# AnalogTransform.net
KiCad netlist of a schematic drawn in Altium Designer
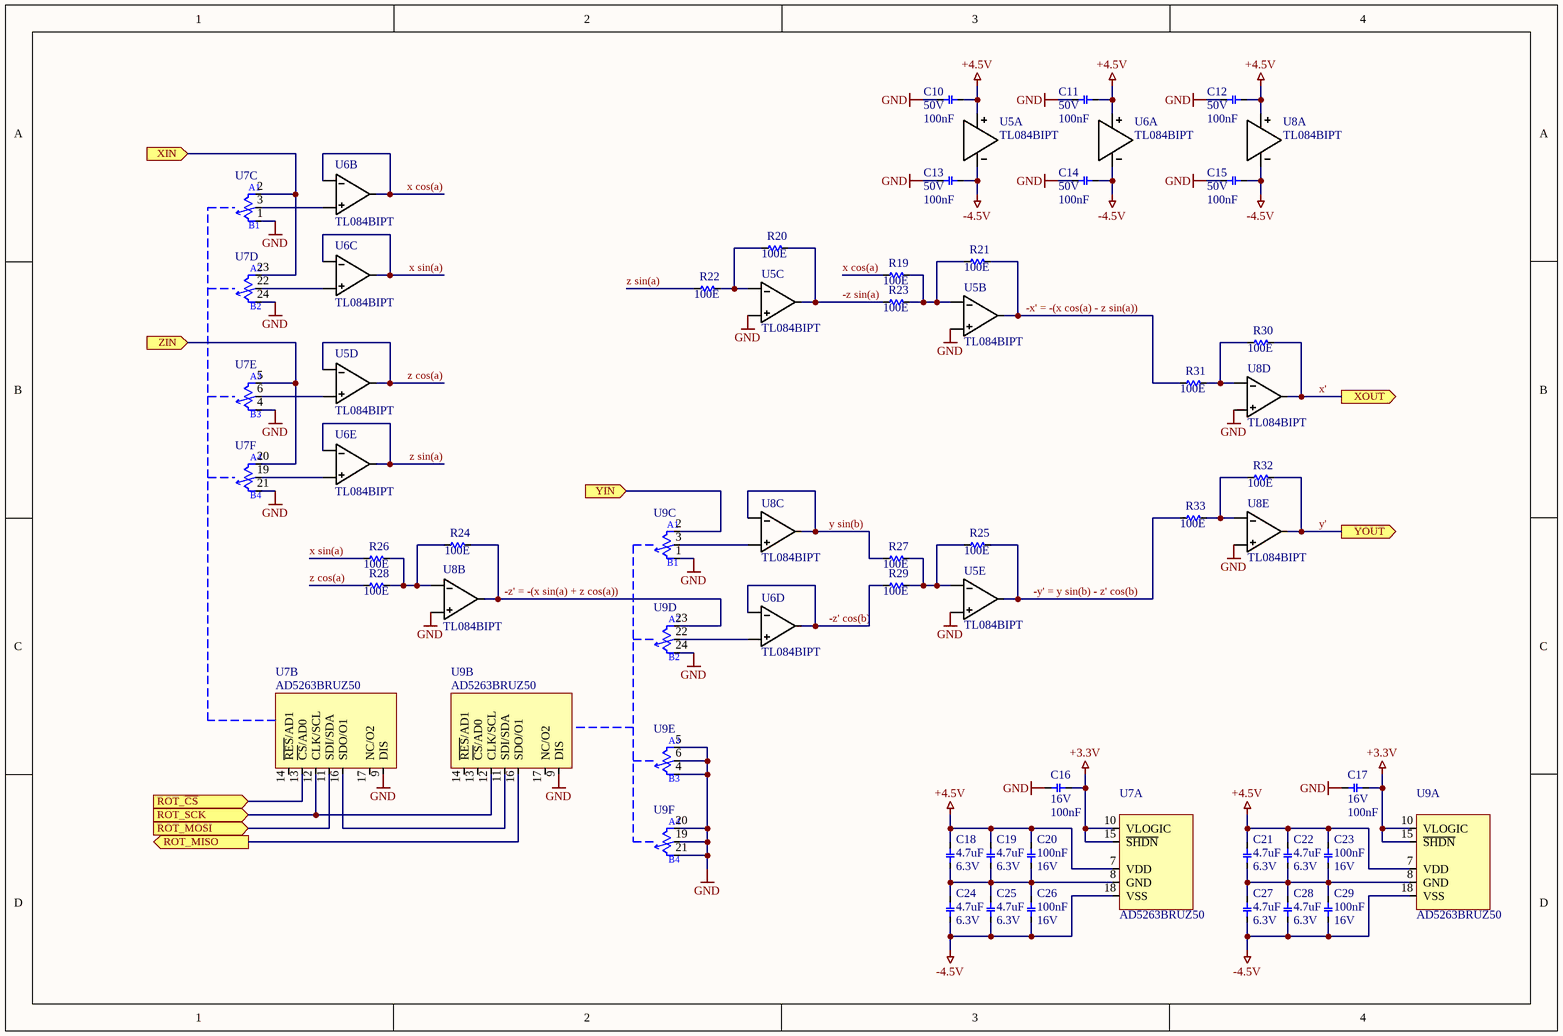
[diagram p0: AnalogTransform.SchDoc]

(export (version "E")
  (design (tool "Eeschema 10.0.6"))
  (components
    (comp (ref "C10")
      (value "100nF")
      (footprint "CX7R0402C")
      (description "SMD Capacitor")
      (fields (field (name "VALUE2") "50V") (field (name "Comment") "04025C104JAT2A"))
      (libsource (lib "ChaoticCircuits") (part "kyocera-C-X7R-0402"))
    )
    (comp (ref "C11")
      (value "100nF")
      (footprint "CX7R0402C")
      (description "SMD Capacitor")
      (fields (field (name "VALUE2") "50V") (field (name "Comment") "04025C104JAT2A"))
      (libsource (lib "ChaoticCircuits") (part "kyocera-C-X7R-0402"))
    )
    (comp (ref "C12")
      (value "100nF")
      (footprint "CX7R0402C")
      (description "SMD Capacitor")
      (fields (field (name "VALUE2") "50V") (field (name "Comment") "04025C104JAT2A"))
      (libsource (lib "ChaoticCircuits") (part "kyocera-C-X7R-0402"))
    )
    (comp (ref "C13")
      (value "100nF")
      (footprint "CX7R0402C")
      (description "SMD Capacitor")
      (fields (field (name "VALUE2") "50V") (field (name "Comment") "04025C104JAT2A"))
      (libsource (lib "ChaoticCircuits") (part "kyocera-C-X7R-0402"))
    )
    (comp (ref "C14")
      (value "100nF")
      (footprint "CX7R0402C")
      (description "SMD Capacitor")
      (fields (field (name "VALUE2") "50V") (field (name "Comment") "04025C104JAT2A"))
      (libsource (lib "ChaoticCircuits") (part "kyocera-C-X7R-0402"))
    )
    (comp (ref "C15")
      (value "100nF")
      (footprint "CX7R0402C")
      (description "SMD Capacitor")
      (fields (field (name "VALUE2") "50V") (field (name "Comment") "04025C104JAT2A"))
      (libsource (lib "ChaoticCircuits") (part "kyocera-C-X7R-0402"))
    )
    (comp (ref "C16")
      (value "100nF")
      (footprint "CX7R0402C")
      (description "SMD Capacitor")
      (fields (field (name "VALUE2") "16V") (field (name "Comment") "0402YC104JAT2A"))
      (libsource (lib "ChaoticCircuits") (part "kyocera-C-X7R-0402"))
    )
    (comp (ref "C17")
      (value "100nF")
      (footprint "CX7R0402C")
      (description "SMD Capacitor")
      (fields (field (name "VALUE2") "16V") (field (name "Comment") "0402YC104JAT2A"))
      (libsource (lib "ChaoticCircuits") (part "kyocera-C-X7R-0402"))
    )
    (comp (ref "C18")
      (value "4.7uF")
      (footprint "CX7R0603K")
      (description "SMD Capacitor")
      (fields (field (name "VALUE2") "6.3V") (field (name "Comment") "06036C475JAT2A"))
      (libsource (lib "ChaoticCircuits") (part "kyocera-C-X7R-0603"))
    )
    (comp (ref "C19")
      (value "4.7uF")
      (footprint "CX7R0603K")
      (description "SMD Capacitor")
      (fields (field (name "VALUE2") "6.3V") (field (name "Comment") "06036C475JAT2A"))
      (libsource (lib "ChaoticCircuits") (part "kyocera-C-X7R-0603"))
    )
    (comp (ref "C20")
      (value "100nF")
      (footprint "CX7R0402C")
      (description "SMD Capacitor")
      (fields (field (name "VALUE2") "16V") (field (name "Comment") "0402YC104JAT2A"))
      (libsource (lib "ChaoticCircuits") (part "kyocera-C-X7R-0402"))
    )
    (comp (ref "C21")
      (value "4.7uF")
      (footprint "CX7R0603K")
      (description "SMD Capacitor")
      (fields (field (name "VALUE2") "6.3V") (field (name "Comment") "06036C475JAT2A"))
      (libsource (lib "ChaoticCircuits") (part "kyocera-C-X7R-0603"))
    )
    (comp (ref "C22")
      (value "4.7uF")
      (footprint "CX7R0603K")
      (description "SMD Capacitor")
      (fields (field (name "VALUE2") "6.3V") (field (name "Comment") "06036C475JAT2A"))
      (libsource (lib "ChaoticCircuits") (part "kyocera-C-X7R-0603"))
    )
    (comp (ref "C23")
      (value "100nF")
      (footprint "CX7R0402C")
      (description "SMD Capacitor")
      (fields (field (name "VALUE2") "16V") (field (name "Comment") "0402YC104JAT2A"))
      (libsource (lib "ChaoticCircuits") (part "kyocera-C-X7R-0402"))
    )
    (comp (ref "C24")
      (value "4.7uF")
      (footprint "CX7R0603K")
      (description "SMD Capacitor")
      (fields (field (name "VALUE2") "6.3V") (field (name "Comment") "06036C475JAT2A"))
      (libsource (lib "ChaoticCircuits") (part "kyocera-C-X7R-0603"))
    )
    (comp (ref "C25")
      (value "4.7uF")
      (footprint "CX7R0603K")
      (description "SMD Capacitor")
      (fields (field (name "VALUE2") "6.3V") (field (name "Comment") "06036C475JAT2A"))
      (libsource (lib "ChaoticCircuits") (part "kyocera-C-X7R-0603"))
    )
    (comp (ref "C26")
      (value "100nF")
      (footprint "CX7R0402C")
      (description "SMD Capacitor")
      (fields (field (name "VALUE2") "16V") (field (name "Comment") "0402YC104JAT2A"))
      (libsource (lib "ChaoticCircuits") (part "kyocera-C-X7R-0402"))
    )
    (comp (ref "C27")
      (value "4.7uF")
      (footprint "CX7R0603K")
      (description "SMD Capacitor")
      (fields (field (name "VALUE2") "6.3V") (field (name "Comment") "06036C475JAT2A"))
      (libsource (lib "ChaoticCircuits") (part "kyocera-C-X7R-0603"))
    )
    (comp (ref "C28")
      (value "4.7uF")
      (footprint "CX7R0603K")
      (description "SMD Capacitor")
      (fields (field (name "VALUE2") "6.3V") (field (name "Comment") "06036C475JAT2A"))
      (libsource (lib "ChaoticCircuits") (part "kyocera-C-X7R-0603"))
    )
    (comp (ref "C29")
      (value "100nF")
      (footprint "CX7R0402C")
      (description "SMD Capacitor")
      (fields (field (name "VALUE2") "16V") (field (name "Comment") "0402YC104JAT2A"))
      (libsource (lib "ChaoticCircuits") (part "kyocera-C-X7R-0402"))
    )
    (comp (ref "R19")
      (value "100E")
      (footprint "RC0402")
      (description "SMD Resistor")
      (fields (field (name "Comment") "0402FR-07100RL"))
      (libsource (lib "ChaoticCircuits") (part "YAGEO-RC-0402"))
    )
    (comp (ref "R20")
      (value "100E")
      (footprint "RC0402")
      (description "SMD Resistor")
      (fields (field (name "Comment") "0402FR-07100RL"))
      (libsource (lib "ChaoticCircuits") (part "YAGEO-RC-0402"))
    )
    (comp (ref "R21")
      (value "100E")
      (footprint "RC0402")
      (description "SMD Resistor")
      (fields (field (name "Comment") "0402FR-07100RL"))
      (libsource (lib "ChaoticCircuits") (part "YAGEO-RC-0402"))
    )
    (comp (ref "R22")
      (value "100E")
      (footprint "RC0402")
      (description "SMD Resistor")
      (fields (field (name "Comment") "0402FR-07100RL"))
      (libsource (lib "ChaoticCircuits") (part "YAGEO-RC-0402"))
    )
    (comp (ref "R23")
      (value "100E")
      (footprint "RC0402")
      (description "SMD Resistor")
      (fields (field (name "Comment") "0402FR-07100RL"))
      (libsource (lib "ChaoticCircuits") (part "YAGEO-RC-0402"))
    )
    (comp (ref "R24")
      (value "100E")
      (footprint "RC0402")
      (description "SMD Resistor")
      (fields (field (name "Comment") "0402FR-07100RL"))
      (libsource (lib "ChaoticCircuits") (part "YAGEO-RC-0402"))
    )
    (comp (ref "R25")
      (value "100E")
      (footprint "RC0402")
      (description "SMD Resistor")
      (fields (field (name "Comment") "0402FR-07100RL"))
      (libsource (lib "ChaoticCircuits") (part "YAGEO-RC-0402"))
    )
    (comp (ref "R26")
      (value "100E")
      (footprint "RC0402")
      (description "SMD Resistor")
      (fields (field (name "Comment") "0402FR-07100RL"))
      (libsource (lib "ChaoticCircuits") (part "YAGEO-RC-0402"))
    )
    (comp (ref "R27")
      (value "100E")
      (footprint "RC0402")
      (description "SMD Resistor")
      (fields (field (name "Comment") "0402FR-07100RL"))
      (libsource (lib "ChaoticCircuits") (part "YAGEO-RC-0402"))
    )
    (comp (ref "R28")
      (value "100E")
      (footprint "RC0402")
      (description "SMD Resistor")
      (fields (field (name "Comment") "0402FR-07100RL"))
      (libsource (lib "ChaoticCircuits") (part "YAGEO-RC-0402"))
    )
    (comp (ref "R29")
      (value "100E")
      (footprint "RC0402")
      (description "SMD Resistor")
      (fields (field (name "Comment") "0402FR-07100RL"))
      (libsource (lib "ChaoticCircuits") (part "YAGEO-RC-0402"))
    )
    (comp (ref "R30")
      (value "100E")
      (footprint "RC0402")
      (description "SMD Resistor")
      (fields (field (name "Comment") "0402FR-07100RL"))
      (libsource (lib "ChaoticCircuits") (part "YAGEO-RC-0402"))
    )
    (comp (ref "R31")
      (value "100E")
      (footprint "RC0402")
      (description "SMD Resistor")
      (fields (field (name "Comment") "0402FR-07100RL"))
      (libsource (lib "ChaoticCircuits") (part "YAGEO-RC-0402"))
    )
    (comp (ref "R32")
      (value "100E")
      (footprint "RC0402")
      (description "SMD Resistor")
      (fields (field (name "Comment") "0402FR-07100RL"))
      (libsource (lib "ChaoticCircuits") (part "YAGEO-RC-0402"))
    )
    (comp (ref "R33")
      (value "100E")
      (footprint "RC0402")
      (description "SMD Resistor")
      (fields (field (name "Comment") "0402FR-07100RL"))
      (libsource (lib "ChaoticCircuits") (part "YAGEO-RC-0402"))
    )
    (comp (ref "U5")
      (value "TL084BIPT")
      (footprint "TSSOP14_0.65_C")
      (description "J-FET Amplifier 4 Circuit - 14-TSSOP")
      (libsource (lib "ChaoticCircuits") (part "TL084"))
    )
    (comp (ref "U6")
      (value "TL084BIPT")
      (footprint "TSSOP14_0.65_C")
      (description "J-FET Amplifier 4 Circuit - 14-TSSOP")
      (libsource (lib "ChaoticCircuits") (part "TL084"))
    )
    (comp (ref "U7")
      (value "AD5263BRUZ50")
      (footprint "TSSOP24_0.65_C")
      (description "Digital Potentiometer 50k Ohm 4 Circuit 256 Taps I²C, SPI Interface 24-TSSOP")
      (libsource (lib "") (part "AD5263BRUZ50_1"))
    )
    (comp (ref "U8")
      (value "TL084BIPT")
      (footprint "TSSOP14_0.65_C")
      (description "J-FET Amplifier 4 Circuit - 14-TSSOP")
      (libsource (lib "ChaoticCircuits") (part "TL084"))
    )
    (comp (ref "U9")
      (value "AD5263BRUZ50")
      (footprint "TSSOP24_0.65_C")
      (description "Digital Potentiometer 50k Ohm 4 Circuit 256 Taps I²C, SPI Interface 24-TSSOP")
      (libsource (lib "ChaoticCircuits") (part "AD5263BRUZ50"))
    )
  )
  (nets
    (net (code "1") (name "+3.3V") (class "Default")
      (node (ref "C16") (pin "2") (pinfunction "2_2") (pintype "passive"))
      (node (ref "C17") (pin "2") (pinfunction "2_2") (pintype "passive"))
      (node (ref "U7") (pin "10") (pinfunction "VLOGIC_10") (pintype "passive"))
      (node (ref "U7") (pin "15") (pinfunction "~{SHDN}_15") (pintype "passive"))
      (node (ref "U9") (pin "10") (pinfunction "VLOGIC_10") (pintype "passive"))
      (node (ref "U9") (pin "15") (pinfunction "~{SHDN}_15") (pintype "passive"))
    )
    (net (code "2") (name "+4.5V") (class "Default")
      (node (ref "C10") (pin "2") (pinfunction "2_2") (pintype "passive"))
      (node (ref "C11") (pin "2") (pinfunction "2_2") (pintype "passive"))
      (node (ref "C12") (pin "2") (pinfunction "2_2") (pintype "passive"))
      (node (ref "C18") (pin "2") (pinfunction "2_2") (pintype "passive"))
      (node (ref "C19") (pin "2") (pinfunction "2_2") (pintype "passive"))
      (node (ref "C20") (pin "2") (pinfunction "2_2") (pintype "passive"))
      (node (ref "C21") (pin "2") (pinfunction "2_2") (pintype "passive"))
      (node (ref "C22") (pin "2") (pinfunction "2_2") (pintype "passive"))
      (node (ref "C23") (pin "2") (pinfunction "2_2") (pintype "passive"))
      (node (ref "U5") (pin "4") (pinfunction "VCC+_4") (pintype "passive"))
      (node (ref "U6") (pin "4") (pinfunction "VCC+_4") (pintype "passive"))
      (node (ref "U7") (pin "7") (pinfunction "VDD_7") (pintype "passive"))
      (node (ref "U8") (pin "4") (pinfunction "VCC+_4") (pintype "passive"))
      (node (ref "U9") (pin "7") (pinfunction "VDD_7") (pintype "passive"))
    )
    (net (code "3") (name "-4.5V") (class "Default")
      (node (ref "C13") (pin "2") (pinfunction "2_2") (pintype "passive"))
      (node (ref "C14") (pin "2") (pinfunction "2_2") (pintype "passive"))
      (node (ref "C15") (pin "2") (pinfunction "2_2") (pintype "passive"))
      (node (ref "C24") (pin "1") (pinfunction "1_1") (pintype "passive"))
      (node (ref "C25") (pin "1") (pinfunction "1_1") (pintype "passive"))
      (node (ref "C26") (pin "1") (pinfunction "1_1") (pintype "passive"))
      (node (ref "C27") (pin "1") (pinfunction "1_1") (pintype "passive"))
      (node (ref "C28") (pin "1") (pinfunction "1_1") (pintype "passive"))
      (node (ref "C29") (pin "1") (pinfunction "1_1") (pintype "passive"))
      (node (ref "U5") (pin "11") (pinfunction "VCC-_11") (pintype "passive"))
      (node (ref "U6") (pin "11") (pinfunction "VCC-_11") (pintype "passive"))
      (node (ref "U7") (pin "18") (pinfunction "VSS_18") (pintype "passive"))
      (node (ref "U8") (pin "11") (pinfunction "VCC-_11") (pintype "passive"))
      (node (ref "U9") (pin "18") (pinfunction "VSS_18") (pintype "passive"))
    )
    (net (code "4") (name "/-x' = -(x cos(a) - z sin(a))") (class "Default")
      (node (ref "R21") (pin "2") (pinfunction "2_2") (pintype "passive"))
      (node (ref "R31") (pin "1") (pinfunction "1_1") (pintype "passive"))
      (node (ref "U5") (pin "1") (pinfunction "OUT1_1") (pintype "passive"))
    )
    (net (code "5") (name "/-y' = y sin(b) - z' cos(b)") (class "Default")
      (node (ref "R25") (pin "2") (pinfunction "2_2") (pintype "passive"))
      (node (ref "R33") (pin "1") (pinfunction "1_1") (pintype "passive"))
      (node (ref "U5") (pin "14") (pinfunction "OUT4_14") (pintype "passive"))
    )
    (net (code "6") (name "/-z sin(a)") (class "Default")
      (node (ref "R20") (pin "2") (pinfunction "2_2") (pintype "passive"))
      (node (ref "R23") (pin "1") (pinfunction "1_1") (pintype "passive"))
      (node (ref "U5") (pin "7") (pinfunction "OUT2_7") (pintype "passive"))
    )
    (net (code "7") (name "/-z' = -(x sin(a) + z cos(a))") (class "Default")
      (node (ref "R24") (pin "2") (pinfunction "2_2") (pintype "passive"))
      (node (ref "U8") (pin "1") (pinfunction "OUT1_1") (pintype "passive"))
      (node (ref "U9") (pin "23") (pinfunction "A2_23") (pintype "passive"))
    )
    (net (code "8") (name "/-z' cos(b)") (class "Default")
      (node (ref "R29") (pin "1") (pinfunction "1_1") (pintype "passive"))
      (node (ref "U6") (pin "8") (pinfunction "OUT3_8") (pintype "passive"))
      (node (ref "U6") (pin "9") (pinfunction "IN3-_9") (pintype "passive"))
    )
    (net (code "9") (name "/ROT_MISO") (class "Default")
      (node (ref "U9") (pin "16") (pinfunction "SDO/O1_16") (pintype "passive"))
    )
    (net (code "10") (name "/ROT_MOSI") (class "Default")
      (node (ref "U7") (pin "11") (pinfunction "SDI/SDA_11") (pintype "passive"))
    )
    (net (code "11") (name "/ROT_SCK") (class "Default")
      (node (ref "U7") (pin "12") (pinfunction "CLK/SCL_12") (pintype "passive"))
      (node (ref "U9") (pin "12") (pinfunction "CLK/SCL_12") (pintype "passive"))
    )
    (net (code "12") (name "/ROT_~{CS}") (class "Default")
      (node (ref "U7") (pin "13") (pinfunction "~{CS}/AD0_13") (pintype "passive"))
    )
    (net (code "13") (name "/XIN") (class "Default")
      (node (ref "U7") (pin "2") (pinfunction "A1_2") (pintype "passive"))
      (node (ref "U7") (pin "23") (pinfunction "A2_23") (pintype "passive"))
    )
    (net (code "14") (name "/YIN") (class "Default")
      (node (ref "U9") (pin "2") (pinfunction "A1_2") (pintype "passive"))
    )
    (net (code "15") (name "/ZIN") (class "Default")
      (node (ref "U7") (pin "20") (pinfunction "A4_20") (pintype "passive"))
      (node (ref "U7") (pin "5") (pinfunction "A3_5") (pintype "passive"))
    )
    (net (code "16") (name "/x cos(a)") (class "Default")
      (node (ref "R19") (pin "1") (pinfunction "1_1") (pintype "passive"))
      (node (ref "U6") (pin "1") (pinfunction "OUT1_1") (pintype "passive"))
      (node (ref "U6") (pin "2") (pinfunction "IN1-_2") (pintype "passive"))
    )
    (net (code "17") (name "/x sin(a)") (class "Default")
      (node (ref "R26") (pin "1") (pinfunction "1_1") (pintype "passive"))
      (node (ref "U6") (pin "6") (pinfunction "IN2-_6") (pintype "passive"))
      (node (ref "U6") (pin "7") (pinfunction "OUT2_7") (pintype "passive"))
    )
    (net (code "18") (name "/x'") (class "Default")
      (node (ref "R30") (pin "2") (pinfunction "2_2") (pintype "passive"))
      (node (ref "U8") (pin "8") (pinfunction "OUT3_8") (pintype "passive"))
    )
    (net (code "19") (name "/y sin(b)") (class "Default")
      (node (ref "R27") (pin "1") (pinfunction "1_1") (pintype "passive"))
      (node (ref "U8") (pin "6") (pinfunction "IN2-_6") (pintype "passive"))
      (node (ref "U8") (pin "7") (pinfunction "OUT2_7") (pintype "passive"))
    )
    (net (code "20") (name "/y'") (class "Default")
      (node (ref "R32") (pin "2") (pinfunction "2_2") (pintype "passive"))
      (node (ref "U8") (pin "14") (pinfunction "OUT4_14") (pintype "passive"))
    )
    (net (code "21") (name "/z cos(a)") (class "Default")
      (node (ref "R28") (pin "1") (pinfunction "1_1") (pintype "passive"))
      (node (ref "U5") (pin "8") (pinfunction "OUT3_8") (pintype "passive"))
      (node (ref "U5") (pin "9") (pinfunction "IN3-_9") (pintype "passive"))
    )
    (net (code "22") (name "/z sin(a)") (class "Default")
      (node (ref "R22") (pin "1") (pinfunction "1_1") (pintype "passive"))
      (node (ref "U6") (pin "13") (pinfunction "IN4-_13") (pintype "passive"))
      (node (ref "U6") (pin "14") (pinfunction "OUT4_14") (pintype "passive"))
    )
    (net (code "23") (name "GND") (class "Default")
      (node (ref "C10") (pin "1") (pinfunction "1_1") (pintype "passive"))
      (node (ref "C11") (pin "1") (pinfunction "1_1") (pintype "passive"))
      (node (ref "C12") (pin "1") (pinfunction "1_1") (pintype "passive"))
      (node (ref "C13") (pin "1") (pinfunction "1_1") (pintype "passive"))
      (node (ref "C14") (pin "1") (pinfunction "1_1") (pintype "passive"))
      (node (ref "C15") (pin "1") (pinfunction "1_1") (pintype "passive"))
      (node (ref "C16") (pin "1") (pinfunction "1_1") (pintype "passive"))
      (node (ref "C17") (pin "1") (pinfunction "1_1") (pintype "passive"))
      (node (ref "U5") (pin "12") (pinfunction "IN4+_12") (pintype "passive"))
      (node (ref "U5") (pin "3") (pinfunction "IN1+_3") (pintype "passive"))
      (node (ref "U5") (pin "5") (pinfunction "IN2+_5") (pintype "passive"))
      (node (ref "U7") (pin "1") (pinfunction "B1_1") (pintype "passive"))
      (node (ref "U7") (pin "21") (pinfunction "B4_21") (pintype "passive"))
      (node (ref "U7") (pin "24") (pinfunction "B2_24") (pintype "passive"))
      (node (ref "U7") (pin "4") (pinfunction "B3_4") (pintype "passive"))
      (node (ref "U7") (pin "9") (pinfunction "DIS_9") (pintype "passive"))
      (node (ref "U8") (pin "10") (pinfunction "IN3+_10") (pintype "passive"))
      (node (ref "U8") (pin "12") (pinfunction "IN4+_12") (pintype "passive"))
      (node (ref "U8") (pin "3") (pinfunction "IN1+_3") (pintype "passive"))
      (node (ref "U9") (pin "1") (pinfunction "B1_1") (pintype "passive"))
      (node (ref "U9") (pin "19") (pinfunction "W4_19") (pintype "passive"))
      (node (ref "U9") (pin "20") (pinfunction "A4_20") (pintype "passive"))
      (node (ref "U9") (pin "21") (pinfunction "B4_21") (pintype "passive"))
      (node (ref "U9") (pin "24") (pinfunction "B2_24") (pintype "passive"))
      (node (ref "U9") (pin "4") (pinfunction "B3_4") (pintype "passive"))
      (node (ref "U9") (pin "5") (pinfunction "A3_5") (pintype "passive"))
      (node (ref "U9") (pin "6") (pinfunction "W3_6") (pintype "passive"))
      (node (ref "U9") (pin "9") (pinfunction "DIS_9") (pintype "passive"))
    )
    (net (code "24") (name "Net-(U5B-IN1-)") (class "Default")
      (node (ref "R19") (pin "2") (pinfunction "2_2") (pintype "passive"))
      (node (ref "R21") (pin "1") (pinfunction "1_1") (pintype "passive"))
      (node (ref "R23") (pin "2") (pinfunction "2_2") (pintype "passive"))
      (node (ref "U5") (pin "2") (pinfunction "IN1-_2") (pintype "passive"))
    )
    (net (code "25") (name "Net-(U5C-IN2-)") (class "Default")
      (node (ref "R20") (pin "1") (pinfunction "1_1") (pintype "passive"))
      (node (ref "R22") (pin "2") (pinfunction "2_2") (pintype "passive"))
      (node (ref "U5") (pin "6") (pinfunction "IN2-_6") (pintype "passive"))
    )
    (net (code "26") (name "Net-(U5D-IN3+)") (class "Default")
      (node (ref "U5") (pin "10") (pinfunction "IN3+_10") (pintype "passive"))
      (node (ref "U7") (pin "6") (pinfunction "W3_6") (pintype "passive"))
    )
    (net (code "27") (name "Net-(U5E-IN4-)") (class "Default")
      (node (ref "R25") (pin "1") (pinfunction "1_1") (pintype "passive"))
      (node (ref "R27") (pin "2") (pinfunction "2_2") (pintype "passive"))
      (node (ref "R29") (pin "2") (pinfunction "2_2") (pintype "passive"))
      (node (ref "U5") (pin "13") (pinfunction "IN4-_13") (pintype "passive"))
    )
    (net (code "28") (name "Net-(U6B-IN1+)") (class "Default")
      (node (ref "U6") (pin "3") (pinfunction "IN1+_3") (pintype "passive"))
      (node (ref "U7") (pin "3") (pinfunction "W1_3") (pintype "passive"))
    )
    (net (code "29") (name "Net-(U6C-IN2+)") (class "Default")
      (node (ref "U6") (pin "5") (pinfunction "IN2+_5") (pintype "passive"))
      (node (ref "U7") (pin "22") (pinfunction "W2_22") (pintype "passive"))
    )
    (net (code "30") (name "Net-(U6D-IN3+)") (class "Default")
      (node (ref "U6") (pin "10") (pinfunction "IN3+_10") (pintype "passive"))
      (node (ref "U9") (pin "22") (pinfunction "W2_22") (pintype "passive"))
    )
    (net (code "31") (name "Net-(U6E-IN4+)") (class "Default")
      (node (ref "U6") (pin "12") (pinfunction "IN4+_12") (pintype "passive"))
      (node (ref "U7") (pin "19") (pinfunction "W4_19") (pintype "passive"))
    )
    (net (code "32") (name "Net-(U7A-GND)") (class "Default")
      (node (ref "C18") (pin "1") (pinfunction "1_1") (pintype "passive"))
      (node (ref "C19") (pin "1") (pinfunction "1_1") (pintype "passive"))
      (node (ref "C20") (pin "1") (pinfunction "1_1") (pintype "passive"))
      (node (ref "C24") (pin "2") (pinfunction "2_2") (pintype "passive"))
      (node (ref "C25") (pin "2") (pinfunction "2_2") (pintype "passive"))
      (node (ref "C26") (pin "2") (pinfunction "2_2") (pintype "passive"))
      (node (ref "U7") (pin "8") (pinfunction "GND_8") (pintype "passive"))
    )
    (net (code "33") (name "Net-(U7B-SDO{slash}O1)") (class "Default")
      (node (ref "U7") (pin "16") (pinfunction "SDO/O1_16") (pintype "passive"))
      (node (ref "U9") (pin "11") (pinfunction "SDI/SDA_11") (pintype "passive"))
    )
    (net (code "34") (name "Net-(U8B-IN1-)") (class "Default")
      (node (ref "R24") (pin "1") (pinfunction "1_1") (pintype "passive"))
      (node (ref "R26") (pin "2") (pinfunction "2_2") (pintype "passive"))
      (node (ref "R28") (pin "2") (pinfunction "2_2") (pintype "passive"))
      (node (ref "U8") (pin "2") (pinfunction "IN1-_2") (pintype "passive"))
    )
    (net (code "35") (name "Net-(U8C-IN2+)") (class "Default")
      (node (ref "U8") (pin "5") (pinfunction "IN2+_5") (pintype "passive"))
      (node (ref "U9") (pin "3") (pinfunction "W1_3") (pintype "passive"))
    )
    (net (code "36") (name "Net-(U8D-IN3-)") (class "Default")
      (node (ref "R30") (pin "1") (pinfunction "1_1") (pintype "passive"))
      (node (ref "R31") (pin "2") (pinfunction "2_2") (pintype "passive"))
      (node (ref "U8") (pin "9") (pinfunction "IN3-_9") (pintype "passive"))
    )
    (net (code "37") (name "Net-(U8E-IN4-)") (class "Default")
      (node (ref "R32") (pin "1") (pinfunction "1_1") (pintype "passive"))
      (node (ref "R33") (pin "2") (pinfunction "2_2") (pintype "passive"))
      (node (ref "U8") (pin "13") (pinfunction "IN4-_13") (pintype "passive"))
    )
    (net (code "38") (name "Net-(U9A-GND)") (class "Default")
      (node (ref "C21") (pin "1") (pinfunction "1_1") (pintype "passive"))
      (node (ref "C22") (pin "1") (pinfunction "1_1") (pintype "passive"))
      (node (ref "C23") (pin "1") (pinfunction "1_1") (pintype "passive"))
      (node (ref "C27") (pin "2") (pinfunction "2_2") (pintype "passive"))
      (node (ref "C28") (pin "2") (pinfunction "2_2") (pintype "passive"))
      (node (ref "C29") (pin "2") (pinfunction "2_2") (pintype "passive"))
      (node (ref "U9") (pin "8") (pinfunction "GND_8") (pintype "passive"))
    )
    (net (code "39") (name "unconnected-(U7B-NC{slash}O2-Pad17)") (class "Default")
      (node (ref "U7") (pin "17") (pinfunction "NC/O2_17") (pintype "passive"))
    )
    (net (code "40") (name "unconnected-(U7B-~{RES}{slash}AD1-Pad14)") (class "Default")
      (node (ref "U7") (pin "14") (pinfunction "~{RES}/AD1_14") (pintype "passive"))
    )
    (net (code "41") (name "unconnected-(U9B-NC{slash}O2-Pad17)") (class "Default")
      (node (ref "U9") (pin "17") (pinfunction "NC/O2_17") (pintype "passive"))
    )
    (net (code "42") (name "unconnected-(U9B-~{CS}{slash}AD0-Pad13)") (class "Default")
      (node (ref "U9") (pin "13") (pinfunction "~{CS}/AD0_13") (pintype "passive"))
    )
    (net (code "43") (name "unconnected-(U9B-~{RES}{slash}AD1-Pad14)") (class "Default")
      (node (ref "U9") (pin "14") (pinfunction "~{RES}/AD1_14") (pintype "passive"))
    )
  )
)
